# MMC56x3_rev_A.net
KiCad netlist of a schematic drawn in EAGLE
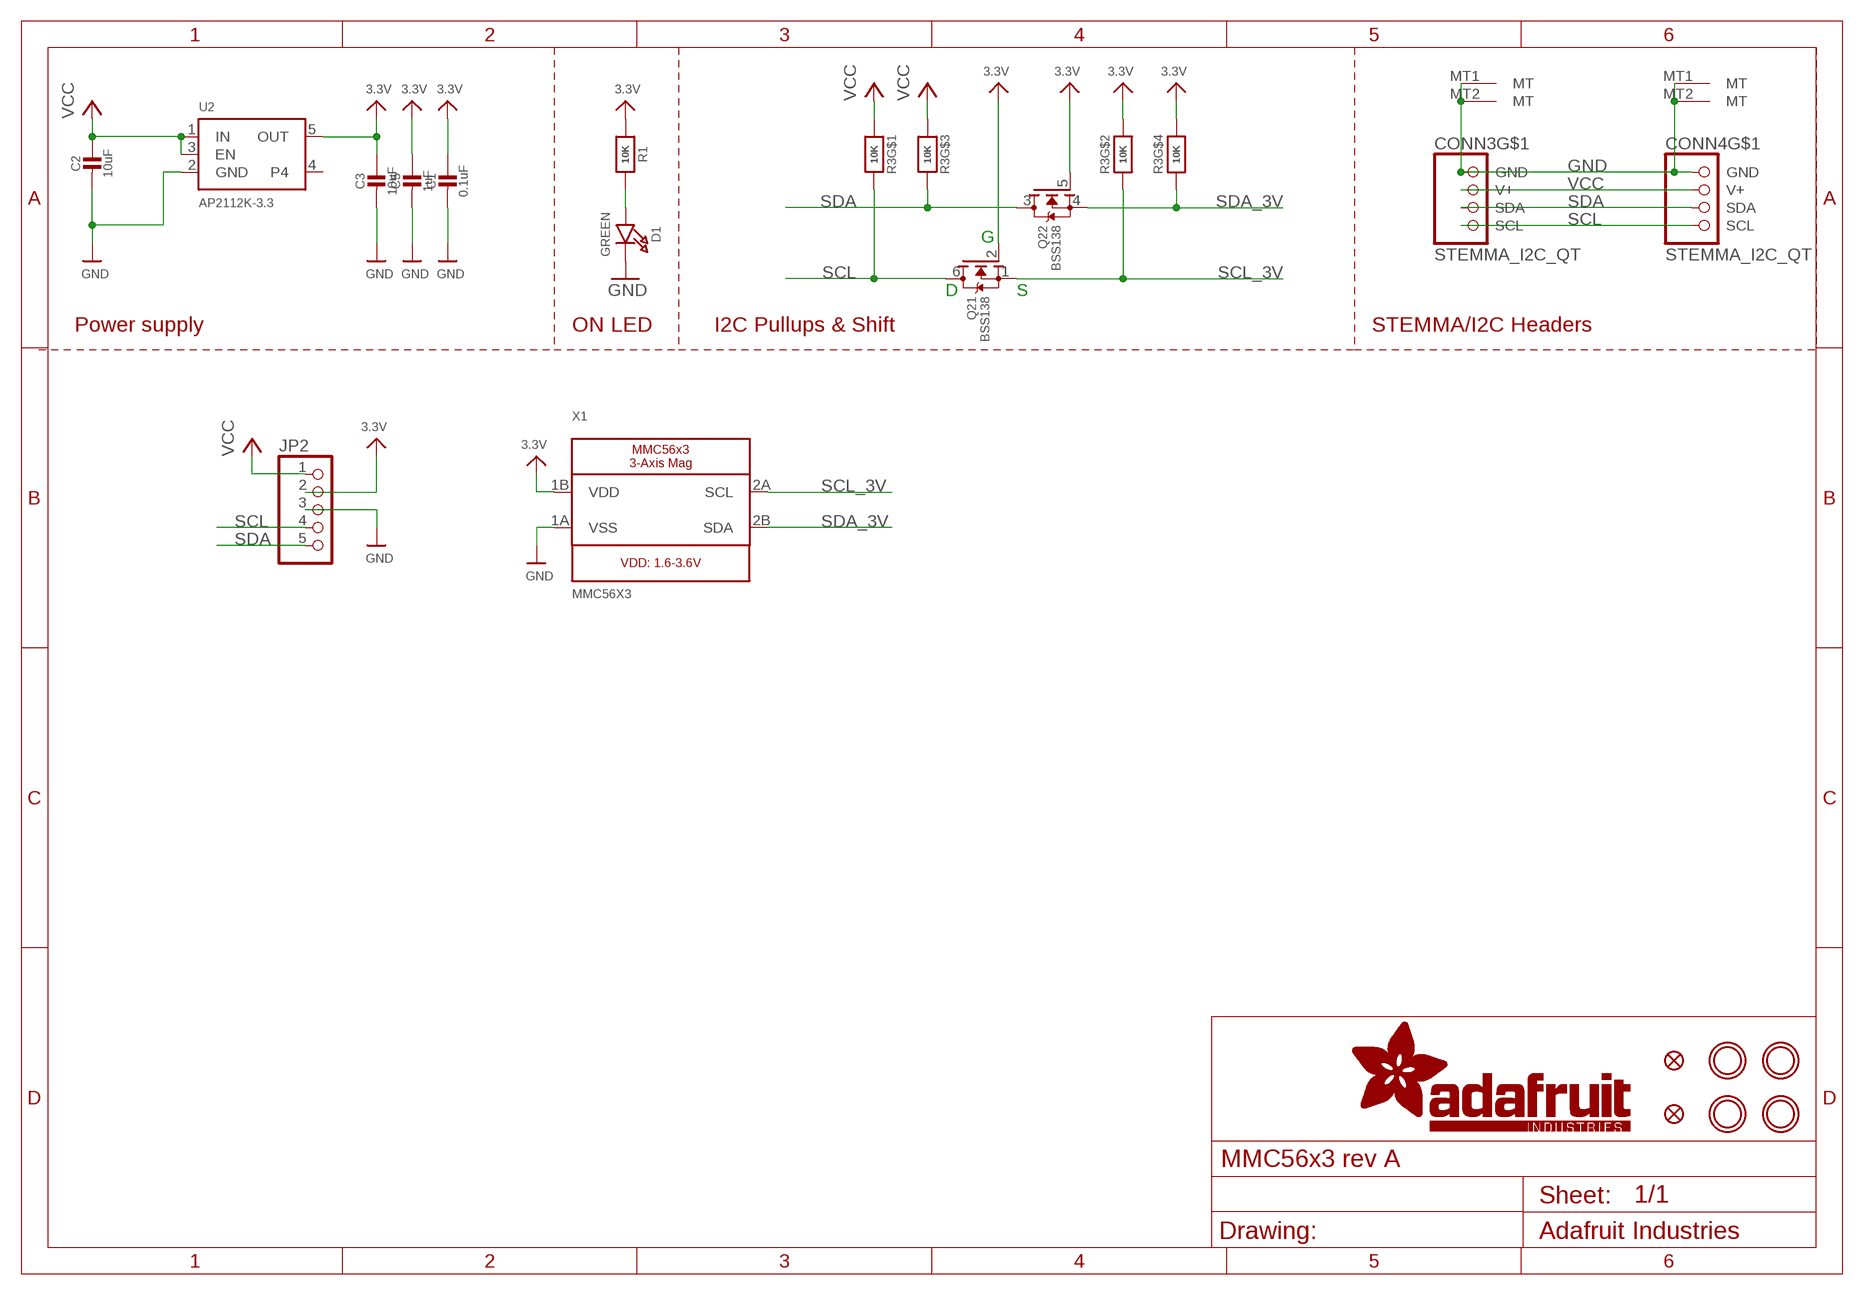
[diagram p0: schematic, sheet 1]

(export (version "E")
  (design (tool "Eeschema 10.0.6"))
  (components
    (comp (ref "C1")
      (value "0.1uF")
      (footprint "eagle-import:0603-NO")
      (libsource (lib "eagle-import") (part "CAP_CERAMIC0603_NO"))
    )
    (comp (ref "C2")
      (value "10uF")
      (footprint "eagle-import:0805-NO")
      (libsource (lib "eagle-import") (part "CAP_CERAMIC0805-NOOUTLINE"))
    )
    (comp (ref "C3")
      (value "10uF")
      (footprint "eagle-import:0805-NO")
      (libsource (lib "eagle-import") (part "CAP_CERAMIC0805-NOOUTLINE"))
    )
    (comp (ref "C5")
      (value "1uF")
      (footprint "eagle-import:0603-NO")
      (libsource (lib "eagle-import") (part "CAP_CERAMIC0603_NO"))
    )
    (comp (ref "CONN3")
      (value "STEMMA_I2C_QT")
      (footprint "eagle-import:JST_SH4")
      (libsource (lib "eagle-import") (part "STEMMA_I2C_QT"))
    )
    (comp (ref "CONN4")
      (value "STEMMA_I2C_QT")
      (footprint "eagle-import:JST_SH4")
      (libsource (lib "eagle-import") (part "STEMMA_I2C_QT"))
    )
    (comp (ref "D1")
      (value "GREEN")
      (footprint "eagle-import:CHIPLED_0603_NOOUTLINE")
      (libsource (lib "eagle-import") (part "LED0603_NOOUTLINE"))
    )
    (comp (ref "FID3")
      (value "FIDUCIAL_1MM")
      (footprint "eagle-import:FIDUCIAL_1MM")
      (libsource (lib "eagle-import") (part "FIDUCIAL_1MM"))
    )
    (comp (ref "FID4")
      (value "FIDUCIAL_1MM")
      (footprint "eagle-import:FIDUCIAL_1MM")
      (libsource (lib "eagle-import") (part "FIDUCIAL_1MM"))
    )
    (comp (ref "JP2")
      (value "HEADER-1X570MIL")
      (footprint "eagle-import:1X05_ROUND_70")
      (libsource (lib "eagle-import") (part "HEADER-1X570MIL"))
    )
    (comp (ref "Q2")
      (value "BSS138")
      (footprint "eagle-import:SOT363")
      (libsource (lib "eagle-import") (part "MOSFET-N_DUAL"))
    )
    (comp (ref "R1")
      (value "10K")
      (footprint "eagle-import:0603-NO")
      (libsource (lib "eagle-import") (part "RESISTOR_0603_NOOUT"))
    )
    (comp (ref "R3")
      (value "10K")
      (footprint "eagle-import:RESPACK_4X0603")
      (libsource (lib "eagle-import") (part "RESISTOR_4PACK"))
    )
    (comp (ref "U$1")
      (value "MOUNTINGHOLE2.5")
      (footprint "eagle-import:MOUNTINGHOLE_2.5_PLATED")
      (libsource (lib "eagle-import") (part "MOUNTINGHOLE2.5"))
    )
    (comp (ref "U$2")
      (value "MOUNTINGHOLE2.5")
      (footprint "eagle-import:MOUNTINGHOLE_2.5_PLATED")
      (libsource (lib "eagle-import") (part "MOUNTINGHOLE2.5"))
    )
    (comp (ref "U$4")
      (value "MOUNTINGHOLE2.5")
      (footprint "eagle-import:MOUNTINGHOLE_2.5_PLATED")
      (libsource (lib "eagle-import") (part "MOUNTINGHOLE2.5"))
    )
    (comp (ref "U$17")
      (value "MOUNTINGHOLE2.5")
      (footprint "eagle-import:MOUNTINGHOLE_2.5_PLATED")
      (libsource (lib "eagle-import") (part "MOUNTINGHOLE2.5"))
    )
    (comp (ref "U2")
      (value "AP2112K-3.3")
      (footprint "eagle-import:SOT23-5")
      (libsource (lib "eagle-import") (part "VREG_SOT23-5"))
    )
    (comp (ref "X1")
      (value "MMC56X3")
      (footprint "eagle-import:WLP-4")
      (libsource (lib "eagle-import") (part "MMC56X3"))
    )
  )
  (nets
    (net (code "1") (name "/SCL") (class "Default")
      (node (ref "CONN3") (pin "4") (pinfunction "SCL_4") (pintype "passive"))
      (node (ref "CONN4") (pin "4") (pinfunction "SCL_4") (pintype "passive"))
      (node (ref "JP2") (pin "4") (pinfunction "4_4") (pintype "passive"))
      (node (ref "Q2") (pin "6") (pinfunction "D_6") (pintype "bidirectional"))
      (node (ref "R3") (pin "8") (pinfunction "2_8") (pintype "passive"))
    )
    (net (code "2") (name "/SCL_3V") (class "Default")
      (node (ref "Q2") (pin "1") (pinfunction "S_1") (pintype "bidirectional"))
      (node (ref "R3") (pin "7") (pinfunction "2_7") (pintype "passive"))
      (node (ref "X1") (pin "2A") (pinfunction "SCL_2A") (pintype "input"))
    )
    (net (code "3") (name "/SDA") (class "Default")
      (node (ref "CONN3") (pin "3") (pinfunction "SDA_3") (pintype "passive"))
      (node (ref "CONN4") (pin "3") (pinfunction "SDA_3") (pintype "passive"))
      (node (ref "JP2") (pin "5") (pinfunction "5_5") (pintype "passive"))
      (node (ref "Q2") (pin "3") (pinfunction "D_3") (pintype "bidirectional"))
      (node (ref "R3") (pin "6") (pinfunction "2_6") (pintype "passive"))
    )
    (net (code "4") (name "/SDA_3V") (class "Default")
      (node (ref "Q2") (pin "4") (pinfunction "S_4") (pintype "bidirectional"))
      (node (ref "R3") (pin "5") (pinfunction "2_5") (pintype "passive"))
      (node (ref "X1") (pin "2B") (pinfunction "SDA_2B") (pintype "bidirectional"))
    )
    (net (code "5") (name "3.3V") (class "Default")
      (node (ref "C1") (pin "1") (pinfunction "1_1") (pintype "passive"))
      (node (ref "C3") (pin "1") (pinfunction "1_1") (pintype "passive"))
      (node (ref "C5") (pin "1") (pinfunction "1_1") (pintype "passive"))
      (node (ref "JP2") (pin "2") (pinfunction "2_2") (pintype "passive"))
      (node (ref "Q2") (pin "2") (pinfunction "G_2") (pintype "bidirectional"))
      (node (ref "Q2") (pin "5") (pinfunction "G_5") (pintype "bidirectional"))
      (node (ref "R1") (pin "1") (pinfunction "1_1") (pintype "passive"))
      (node (ref "R3") (pin "2") (pinfunction "1_2") (pintype "passive"))
      (node (ref "R3") (pin "4") (pinfunction "1_4") (pintype "passive"))
      (node (ref "U2") (pin "5") (pinfunction "OUT_5") (pintype "power_in"))
      (node (ref "X1") (pin "1B") (pinfunction "VDD_1B") (pintype "power_in"))
    )
    (net (code "6") (name "GND") (class "Default")
      (node (ref "C1") (pin "2") (pinfunction "2_2") (pintype "passive"))
      (node (ref "C2") (pin "2") (pinfunction "2_2") (pintype "passive"))
      (node (ref "C3") (pin "2") (pinfunction "2_2") (pintype "passive"))
      (node (ref "C5") (pin "2") (pinfunction "2_2") (pintype "passive"))
      (node (ref "CONN3") (pin "1") (pinfunction "GND_1") (pintype "passive"))
      (node (ref "CONN3") (pin "MT1") (pinfunction "MT_MT1") (pintype "bidirectional"))
      (node (ref "CONN3") (pin "MT2") (pinfunction "MT_MT2") (pintype "bidirectional"))
      (node (ref "CONN4") (pin "1") (pinfunction "GND_1") (pintype "passive"))
      (node (ref "CONN4") (pin "MT1") (pinfunction "MT_MT1") (pintype "bidirectional"))
      (node (ref "CONN4") (pin "MT2") (pinfunction "MT_MT2") (pintype "bidirectional"))
      (node (ref "D1") (pin "C") (pinfunction "C_C") (pintype "passive"))
      (node (ref "JP2") (pin "3") (pinfunction "3_3") (pintype "passive"))
      (node (ref "U2") (pin "2") (pinfunction "GND_2") (pintype "power_in"))
      (node (ref "X1") (pin "1A") (pinfunction "VSS_1A") (pintype "power_in"))
    )
    (net (code "7") (name "Net-(D1-PadA)") (class "Default")
      (node (ref "D1") (pin "A") (pinfunction "A_A") (pintype "passive"))
      (node (ref "R1") (pin "2") (pinfunction "2_2") (pintype "passive"))
    )
    (net (code "8") (name "VCC") (class "Default")
      (node (ref "C2") (pin "1") (pinfunction "1_1") (pintype "passive"))
      (node (ref "CONN3") (pin "2") (pinfunction "V+_2") (pintype "passive"))
      (node (ref "CONN4") (pin "2") (pinfunction "V+_2") (pintype "passive"))
      (node (ref "JP2") (pin "1") (pinfunction "1_1") (pintype "passive"))
      (node (ref "R3") (pin "1") (pinfunction "1_1") (pintype "passive"))
      (node (ref "R3") (pin "3") (pinfunction "1_3") (pintype "passive"))
      (node (ref "U2") (pin "1") (pinfunction "IN_1") (pintype "power_in"))
      (node (ref "U2") (pin "3") (pinfunction "EN_3") (pintype "input"))
    )
    (net (code "9") (name "unconnected-(U2-P4-Pad4)") (class "Default")
      (node (ref "U2") (pin "4") (pinfunction "P4_4") (pintype "bidirectional"))
    )
  )
)
